# Sheet1.net
KiCad netlist of a schematic drawn in Altium Designer
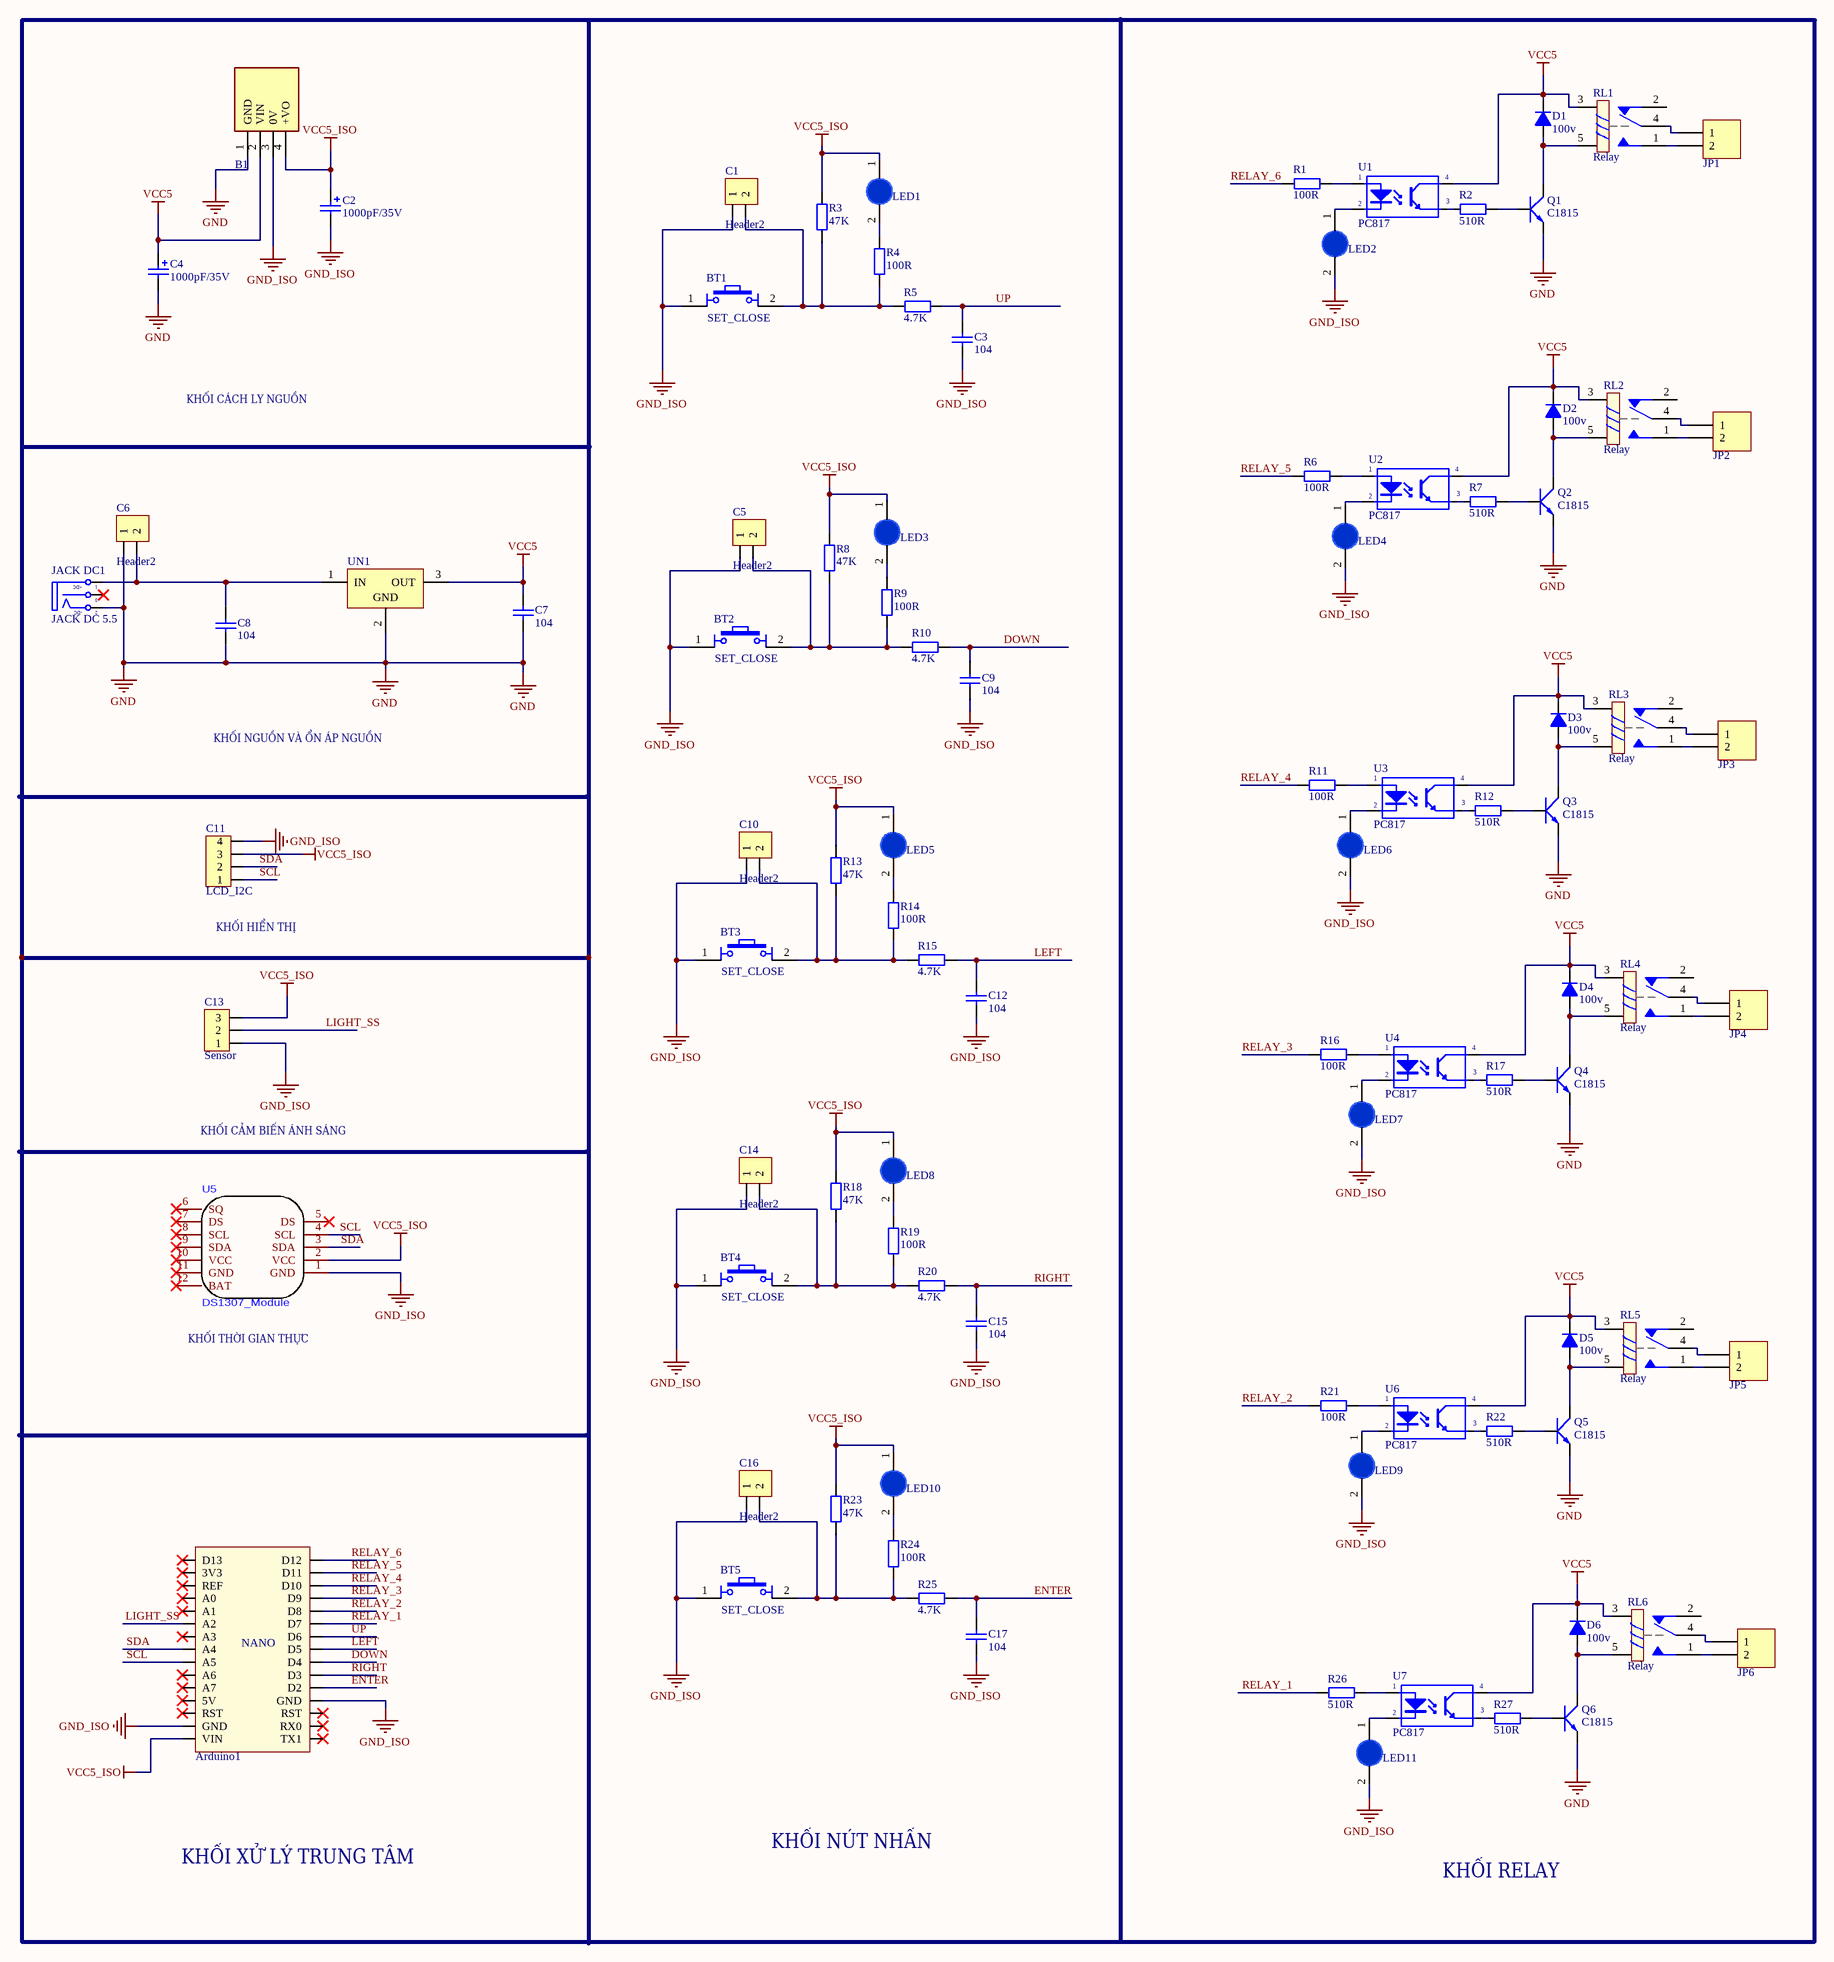
[diagram p0: Sheet1.SchDoc]

(export (version "E")
  (design (tool "Eeschema 10.0.6"))
  (components
    (comp (ref "Arduino1")
      (value "Arduino Nano")
      (footprint "Arduino Nano")
      (description "Arduino NANO")
      (libsource (lib "myLib_v1") (part "Arduino Nano"))
    )
    (comp (ref "B1")
      (value "B0505S1W")
      (footprint "B0505S1W")
      (description "Power Supply")
      (fields (field (name "MANUFACTURER_PART_NUMBER") "B0505S-1W"))
      (libsource (lib "myLib_v1") (part "B0505S1W"))
    )
    (comp (ref "BT1")
      (value "SET_CLOSE")
      (footprint "Nut Nhan 4 Chan Cam 6x6")
      (description "Nut Nhan 4 Chan 6x6mm")
      (libsource (lib "Altium_Lib_by_KhueNguyenCreator") (part "Nut Nhan 4 Chan Cam 6x6"))
    )
    (comp (ref "BT2")
      (value "SET_CLOSE")
      (footprint "Nut Nhan 4 Chan Cam 6x6")
      (description "Nut Nhan 4 Chan 6x6mm")
      (libsource (lib "Altium_Lib_by_KhueNguyenCreator") (part "Nut Nhan 4 Chan Cam 6x6"))
    )
    (comp (ref "BT3")
      (value "SET_CLOSE")
      (footprint "Nut Nhan 4 Chan Cam 6x6")
      (description "Nut Nhan 4 Chan 6x6mm")
      (libsource (lib "Altium_Lib_by_KhueNguyenCreator") (part "Nut Nhan 4 Chan Cam 6x6"))
    )
    (comp (ref "BT4")
      (value "SET_CLOSE")
      (footprint "Nut Nhan 4 Chan Cam 6x6")
      (description "Nut Nhan 4 Chan 6x6mm")
      (libsource (lib "Altium_Lib_by_KhueNguyenCreator") (part "Nut Nhan 4 Chan Cam 6x6"))
    )
    (comp (ref "BT5")
      (value "SET_CLOSE")
      (footprint "Nut Nhan 4 Chan Cam 6x6")
      (description "Nut Nhan 4 Chan 6x6mm")
      (libsource (lib "Altium_Lib_by_KhueNguyenCreator") (part "Nut Nhan 4 Chan Cam 6x6"))
    )
    (comp (ref "C1")
      (value "Header2")
      (footprint "Header2")
      (description "Header IDC, 2 x 1 Pin Vertical 2.54mm Pitch (Non-Boxed, Male)")
      (fields
        (field (name "MANUFACTURER") "Würth Elektronik eiSos GmbH")
        (field (name "PARTNO") "613002143121")
        (field (name "CREATED BY") "Karrer Zheng")
      )
      (libsource (lib "myLib_v1") (part "Header2"))
    )
    (comp (ref "C2")
      (value "1000pF/35V")
      (footprint "CP2/5")
      (description "Polarized Capacitor (Surface Mount)")
      (fields (field (name "Comment") "Cap Pol3") (field (name "PUBLISHER") "Altium Limited"))
      (libsource (lib "myLib_v1") (part "Cap Pol3"))
    )
    (comp (ref "C3")
      (value "104")
      (footprint "tu gom")
      (description "Cắm")
      (libsource (lib "Altium_Lib_by_KhueNguyenCreator") (part "Tu gom 104 50V"))
    )
    (comp (ref "C4")
      (value "1000pF/35V")
      (footprint "CP2/5")
      (description "Polarized Capacitor (Surface Mount)")
      (fields (field (name "Comment") "Cap Pol3") (field (name "PUBLISHER") "Altium Limited"))
      (libsource (lib "myLib_v1") (part "Cap Pol3"))
    )
    (comp (ref "C5")
      (value "Header2")
      (footprint "Header2")
      (description "Header IDC, 2 x 1 Pin Vertical 2.54mm Pitch (Non-Boxed, Male)")
      (fields
        (field (name "MANUFACTURER") "Würth Elektronik eiSos GmbH")
        (field (name "PARTNO") "613002143121")
        (field (name "CREATED BY") "Karrer Zheng")
      )
      (libsource (lib "myLib_v1") (part "Header2"))
    )
    (comp (ref "C6")
      (value "Header2")
      (footprint "Header2")
      (description "Header IDC, 2 x 1 Pin Vertical 2.54mm Pitch (Non-Boxed, Male)")
      (fields
        (field (name "MANUFACTURER") "Würth Elektronik eiSos GmbH")
        (field (name "PARTNO") "613002143121")
        (field (name "CREATED BY") "Karrer Zheng")
      )
      (libsource (lib "myLib_v1") (part "Header2"))
    )
    (comp (ref "C7")
      (value "104")
      (footprint "tu gom")
      (description "Cắm")
      (libsource (lib "Altium_Lib_by_KhueNguyenCreator") (part "Tu gom 104 50V"))
    )
    (comp (ref "C8")
      (value "104")
      (footprint "tu gom")
      (description "Cắm")
      (libsource (lib "Altium_Lib_by_KhueNguyenCreator") (part "Tu gom 104 50V"))
    )
    (comp (ref "C9")
      (value "104")
      (footprint "tu gom")
      (description "Cắm")
      (libsource (lib "Altium_Lib_by_KhueNguyenCreator") (part "Tu gom 104 50V"))
    )
    (comp (ref "C10")
      (value "Header2")
      (footprint "Header2")
      (description "Header IDC, 2 x 1 Pin Vertical 2.54mm Pitch (Non-Boxed, Male)")
      (fields
        (field (name "MANUFACTURER") "Würth Elektronik eiSos GmbH")
        (field (name "PARTNO") "613002143121")
        (field (name "CREATED BY") "Karrer Zheng")
      )
      (libsource (lib "myLib_v1") (part "Header2"))
    )
    (comp (ref "C11")
      (value "LCD_I2C")
      (footprint "Header4")
      (description "Header IDC, 4 x 1 Pin Vertical 2.54mm Pitch (Non-Boxed, Male)")
      (fields
        (field (name "MANUFACTURER") "Würth Elektronik eiSos GmbH")
        (field (name "PARTNO") "613002143121")
        (field (name "CREATED BY") "Karrer Zheng")
      )
      (libsource (lib "myLib_v1") (part "Header4"))
    )
    (comp (ref "C12")
      (value "104")
      (footprint "tu gom")
      (description "Cắm")
      (libsource (lib "Altium_Lib_by_KhueNguyenCreator") (part "Tu gom 104 50V"))
    )
    (comp (ref "C13")
      (value "Sensor")
      (footprint "Header3")
      (description "Header IDC, 3 x 1 Pin Vertical 2.54mm Pitch (Non-Boxed, Male)")
      (fields
        (field (name "MANUFACTURER") "Würth Elektronik eiSos GmbH")
        (field (name "PARTNO") "613002143121")
        (field (name "CREATED BY") "Karrer Zheng")
      )
      (libsource (lib "myLib_v1") (part "Header3"))
    )
    (comp (ref "C14")
      (value "Header2")
      (footprint "Header2")
      (description "Header IDC, 2 x 1 Pin Vertical 2.54mm Pitch (Non-Boxed, Male)")
      (fields
        (field (name "MANUFACTURER") "Würth Elektronik eiSos GmbH")
        (field (name "PARTNO") "613002143121")
        (field (name "CREATED BY") "Karrer Zheng")
      )
      (libsource (lib "myLib_v1") (part "Header2"))
    )
    (comp (ref "C15")
      (value "104")
      (footprint "tu gom")
      (description "Cắm")
      (libsource (lib "Altium_Lib_by_KhueNguyenCreator") (part "Tu gom 104 50V"))
    )
    (comp (ref "C16")
      (value "Header2")
      (footprint "Header2")
      (description "Header IDC, 2 x 1 Pin Vertical 2.54mm Pitch (Non-Boxed, Male)")
      (fields
        (field (name "MANUFACTURER") "Würth Elektronik eiSos GmbH")
        (field (name "PARTNO") "613002143121")
        (field (name "CREATED BY") "Karrer Zheng")
      )
      (libsource (lib "myLib_v1") (part "Header2"))
    )
    (comp (ref "C17")
      (value "104")
      (footprint "tu gom")
      (description "Cắm")
      (libsource (lib "Altium_Lib_by_KhueNguyenCreator") (part "Tu gom 104 50V"))
    )
    (comp (ref "D1")
      (value "100v")
      (footprint "DIODE 0.5A")
      (description "Cắm")
      (libsource (lib "Altium_Lib_by_KhueNguyenCreator") (part "Diode 1N4148"))
    )
    (comp (ref "D2")
      (value "100v")
      (footprint "DIODE 0.5A")
      (description "Cắm")
      (libsource (lib "Altium_Lib_by_KhueNguyenCreator") (part "Diode 1N4148"))
    )
    (comp (ref "D3")
      (value "100v")
      (footprint "DIODE 0.5A")
      (description "Cắm")
      (libsource (lib "Altium_Lib_by_KhueNguyenCreator") (part "Diode 1N4148"))
    )
    (comp (ref "D4")
      (value "100v")
      (footprint "DIODE 0.5A")
      (description "Cắm")
      (libsource (lib "Altium_Lib_by_KhueNguyenCreator") (part "Diode 1N4148"))
    )
    (comp (ref "D5")
      (value "100v")
      (footprint "DIODE 0.5A")
      (description "Cắm")
      (libsource (lib "Altium_Lib_by_KhueNguyenCreator") (part "Diode 1N4148"))
    )
    (comp (ref "D6")
      (value "100v")
      (footprint "DIODE 0.5A")
      (description "Cắm")
      (libsource (lib "Altium_Lib_by_KhueNguyenCreator") (part "Diode 1N4148"))
    )
    (comp (ref "JACK DC1")
      (value "JACK DC 5.5")
      (footprint "JACK DC 5.5")
      (libsource (lib "Altium_Lib_by_KhueNguyenCreator") (part "JACK DC 5.5"))
    )
    (comp (ref "JP1")
      (value "Header 2_1")
      (footprint "HED2")
      (description "Header, 2-Pin")
      (fields (field (name "MANUFACTURER") "Generic Components"))
      (libsource (lib "myLib_v1") (part "Header 2_1"))
    )
    (comp (ref "JP2")
      (value "Header 2_1")
      (footprint "HED2")
      (description "Header, 2-Pin")
      (fields (field (name "MANUFACTURER") "Generic Components"))
      (libsource (lib "myLib_v1") (part "Header 2_1"))
    )
    (comp (ref "JP3")
      (value "Header 2_1")
      (footprint "HED2")
      (description "Header, 2-Pin")
      (fields (field (name "MANUFACTURER") "Generic Components"))
      (libsource (lib "myLib_v1") (part "Header 2_1"))
    )
    (comp (ref "JP4")
      (value "Header 2_1")
      (footprint "HED2")
      (description "Header, 2-Pin")
      (fields (field (name "MANUFACTURER") "Generic Components"))
      (libsource (lib "myLib_v1") (part "Header 2_1"))
    )
    (comp (ref "JP5")
      (value "Header 2_1")
      (footprint "HED2")
      (description "Header, 2-Pin")
      (fields (field (name "MANUFACTURER") "Generic Components"))
      (libsource (lib "myLib_v1") (part "Header 2_1"))
    )
    (comp (ref "JP6")
      (value "Header 2_1")
      (footprint "HED2")
      (description "Header, 2-Pin")
      (fields (field (name "MANUFACTURER") "Generic Components"))
      (libsource (lib "myLib_v1") (part "Header 2_1"))
    )
    (comp (ref "LED1")
      (value "LED 3mm")
      (footprint "LED-3MM-BLUE")
      (description "Cắm")
      (libsource (lib "myLib_v1") (part "LED 3mm Xanh Duong"))
    )
    (comp (ref "LED2")
      (value "LED 3mm")
      (footprint "LED-3MM-BLUE")
      (description "Cắm")
      (libsource (lib "myLib_v1") (part "LED 3mm Xanh Duong"))
    )
    (comp (ref "LED3")
      (value "LED 3mm")
      (footprint "LED-3MM-BLUE")
      (description "Cắm")
      (libsource (lib "myLib_v1") (part "LED 3mm Xanh Duong"))
    )
    (comp (ref "LED4")
      (value "LED 3mm")
      (footprint "LED-3MM-BLUE")
      (description "Cắm")
      (libsource (lib "myLib_v1") (part "LED 3mm Xanh Duong"))
    )
    (comp (ref "LED5")
      (value "LED 3mm")
      (footprint "LED-3MM-BLUE")
      (description "Cắm")
      (libsource (lib "myLib_v1") (part "LED 3mm Xanh Duong"))
    )
    (comp (ref "LED6")
      (value "LED 3mm")
      (footprint "LED-3MM-BLUE")
      (description "Cắm")
      (libsource (lib "myLib_v1") (part "LED 3mm Xanh Duong"))
    )
    (comp (ref "LED7")
      (value "LED 3mm")
      (footprint "LED-3MM-BLUE")
      (description "Cắm")
      (libsource (lib "myLib_v1") (part "LED 3mm Xanh Duong"))
    )
    (comp (ref "LED8")
      (value "LED 3mm")
      (footprint "LED-3MM-BLUE")
      (description "Cắm")
      (libsource (lib "myLib_v1") (part "LED 3mm Xanh Duong"))
    )
    (comp (ref "LED9")
      (value "LED 3mm")
      (footprint "LED-3MM-BLUE")
      (description "Cắm")
      (libsource (lib "myLib_v1") (part "LED 3mm Xanh Duong"))
    )
    (comp (ref "LED10")
      (value "LED 3mm")
      (footprint "LED-3MM-BLUE")
      (description "Cắm")
      (libsource (lib "myLib_v1") (part "LED 3mm Xanh Duong"))
    )
    (comp (ref "LED11")
      (value "LED 3mm")
      (footprint "LED-3MM-BLUE")
      (description "Cắm")
      (libsource (lib "myLib_v1") (part "LED 3mm Xanh Duong"))
    )
    (comp (ref "Q1")
      (value "C1815")
      (footprint "C1815_cam")
      (description "NPN 600mW, ECB")
      (libsource (lib "myLib_v1") (part "C1815"))
    )
    (comp (ref "Q2")
      (value "C1815")
      (footprint "C1815_cam")
      (description "NPN 600mW, ECB")
      (libsource (lib "myLib_v1") (part "C1815"))
    )
    (comp (ref "Q3")
      (value "C1815")
      (footprint "C1815_cam")
      (description "NPN 600mW, ECB")
      (libsource (lib "myLib_v1") (part "C1815"))
    )
    (comp (ref "Q4")
      (value "C1815")
      (footprint "C1815_cam")
      (description "NPN 600mW, ECB")
      (libsource (lib "myLib_v1") (part "C1815"))
    )
    (comp (ref "Q5")
      (value "C1815")
      (footprint "C1815_cam")
      (description "NPN 600mW, ECB")
      (libsource (lib "myLib_v1") (part "C1815"))
    )
    (comp (ref "Q6")
      (value "C1815")
      (footprint "C1815_cam")
      (description "NPN 600mW, ECB")
      (libsource (lib "myLib_v1") (part "C1815"))
    )
    (comp (ref "R1")
      (value "100R")
      (footprint "R1/4W")
      (description "Resistor 1/4W")
      (libsource (lib "myLib_v1") (part "R1/4W"))
    )
    (comp (ref "R2")
      (value "510R")
      (footprint "R1/4W")
      (description "Resistor 1/4W")
      (libsource (lib "myLib_v1") (part "R1/4W"))
    )
    (comp (ref "R3")
      (value "47K")
      (footprint "R1/4W")
      (description "Resistor 1/4W")
      (libsource (lib "myLib_v1") (part "R1/4W"))
    )
    (comp (ref "R4")
      (value "100R")
      (footprint "R1/4W")
      (description "Resistor 1/4W")
      (libsource (lib "myLib_v1") (part "R1/4W"))
    )
    (comp (ref "R5")
      (value "4.7K")
      (footprint "R1/4W")
      (description "Resistor 1/4W")
      (libsource (lib "myLib_v1") (part "R1/4W"))
    )
    (comp (ref "R6")
      (value "100R")
      (footprint "R1/4W")
      (description "Resistor 1/4W")
      (libsource (lib "myLib_v1") (part "R1/4W"))
    )
    (comp (ref "R7")
      (value "510R")
      (footprint "R1/4W")
      (description "Resistor 1/4W")
      (libsource (lib "myLib_v1") (part "R1/4W"))
    )
    (comp (ref "R8")
      (value "47K")
      (footprint "R1/4W")
      (description "Resistor 1/4W")
      (libsource (lib "myLib_v1") (part "R1/4W"))
    )
    (comp (ref "R9")
      (value "100R")
      (footprint "R1/4W")
      (description "Resistor 1/4W")
      (libsource (lib "myLib_v1") (part "R1/4W"))
    )
    (comp (ref "R10")
      (value "4.7K")
      (footprint "R1/4W")
      (description "Resistor 1/4W")
      (libsource (lib "myLib_v1") (part "R1/4W"))
    )
    (comp (ref "R11")
      (value "100R")
      (footprint "R1/4W")
      (description "Resistor 1/4W")
      (libsource (lib "myLib_v1") (part "R1/4W"))
    )
    (comp (ref "R12")
      (value "510R")
      (footprint "R1/4W")
      (description "Resistor 1/4W")
      (libsource (lib "myLib_v1") (part "R1/4W"))
    )
    (comp (ref "R13")
      (value "47K")
      (footprint "R1/4W")
      (description "Resistor 1/4W")
      (libsource (lib "myLib_v1") (part "R1/4W"))
    )
    (comp (ref "R14")
      (value "100R")
      (footprint "R1/4W")
      (description "Resistor 1/4W")
      (libsource (lib "myLib_v1") (part "R1/4W"))
    )
    (comp (ref "R15")
      (value "4.7K")
      (footprint "R1/4W")
      (description "Resistor 1/4W")
      (libsource (lib "myLib_v1") (part "R1/4W"))
    )
    (comp (ref "R16")
      (value "100R")
      (footprint "R1/4W")
      (description "Resistor 1/4W")
      (libsource (lib "myLib_v1") (part "R1/4W"))
    )
    (comp (ref "R17")
      (value "510R")
      (footprint "R1/4W")
      (description "Resistor 1/4W")
      (libsource (lib "myLib_v1") (part "R1/4W"))
    )
    (comp (ref "R18")
      (value "47K")
      (footprint "R1/4W")
      (description "Resistor 1/4W")
      (libsource (lib "myLib_v1") (part "R1/4W"))
    )
    (comp (ref "R19")
      (value "100R")
      (footprint "R1/4W")
      (description "Resistor 1/4W")
      (libsource (lib "myLib_v1") (part "R1/4W"))
    )
    (comp (ref "R20")
      (value "4.7K")
      (footprint "R1/4W")
      (description "Resistor 1/4W")
      (libsource (lib "myLib_v1") (part "R1/4W"))
    )
    (comp (ref "R21")
      (value "100R")
      (footprint "R1/4W")
      (description "Resistor 1/4W")
      (libsource (lib "myLib_v1") (part "R1/4W"))
    )
    (comp (ref "R22")
      (value "510R")
      (footprint "R1/4W")
      (description "Resistor 1/4W")
      (libsource (lib "myLib_v1") (part "R1/4W"))
    )
    (comp (ref "R23")
      (value "47K")
      (footprint "R1/4W")
      (description "Resistor 1/4W")
      (libsource (lib "myLib_v1") (part "R1/4W"))
    )
    (comp (ref "R24")
      (value "100R")
      (footprint "R1/4W")
      (description "Resistor 1/4W")
      (libsource (lib "myLib_v1") (part "R1/4W"))
    )
    (comp (ref "R25")
      (value "4.7K")
      (footprint "R1/4W")
      (description "Resistor 1/4W")
      (libsource (lib "myLib_v1") (part "R1/4W"))
    )
    (comp (ref "R26")
      (value "510R")
      (footprint "R1/4W")
      (description "Resistor 1/4W")
      (libsource (lib "myLib_v1") (part "R1/4W"))
    )
    (comp (ref "R27")
      (value "510R")
      (footprint "R1/4W")
      (description "Resistor 1/4W")
      (libsource (lib "myLib_v1") (part "R1/4W"))
    )
    (comp (ref "RL1")
      (value "Relay")
      (footprint "RELAY_SRA_05VDC_CL")
      (description "Relay 5 Chan")
      (libsource (lib "myLib_v1") (part "RL_SRA-05VDC-CL"))
    )
    (comp (ref "RL2")
      (value "Relay")
      (footprint "RELAY_SRA_05VDC_CL")
      (description "Relay 5 Chan")
      (libsource (lib "myLib_v1") (part "RL_SRA-05VDC-CL"))
    )
    (comp (ref "RL3")
      (value "Relay")
      (footprint "RELAY_SRA_05VDC_CL")
      (description "Relay 5 Chan")
      (libsource (lib "myLib_v1") (part "RL_SRA-05VDC-CL"))
    )
    (comp (ref "RL4")
      (value "Relay")
      (footprint "RELAY_SRA_05VDC_CL")
      (description "Relay 5 Chan")
      (libsource (lib "myLib_v1") (part "RL_SRA-05VDC-CL"))
    )
    (comp (ref "RL5")
      (value "Relay")
      (footprint "RELAY_SRA_05VDC_CL")
      (description "Relay 5 Chan")
      (libsource (lib "myLib_v1") (part "RL_SRA-05VDC-CL"))
    )
    (comp (ref "RL6")
      (value "Relay")
      (footprint "RELAY_SRA_05VDC_CL")
      (description "Relay 5 Chan")
      (libsource (lib "myLib_v1") (part "RL_SRA-05VDC-CL"))
    )
    (comp (ref "U1")
      (value "PC817")
      (footprint "DIP4/W0.3")
      (description "Single Opto")
      (libsource (lib "myLib_v1") (part "PC817"))
    )
    (comp (ref "U2")
      (value "PC817")
      (footprint "DIP4/W0.3")
      (description "Single Opto")
      (libsource (lib "myLib_v1") (part "PC817"))
    )
    (comp (ref "U3")
      (value "PC817")
      (footprint "DIP4/W0.3")
      (description "Single Opto")
      (libsource (lib "myLib_v1") (part "PC817"))
    )
    (comp (ref "U4")
      (value "PC817")
      (footprint "DIP4/W0.3")
      (description "Single Opto")
      (libsource (lib "myLib_v1") (part "PC817"))
    )
    (comp (ref "U5")
      (value "DS1307_Module")
      (footprint "DS1307 MODULE")
      (libsource (lib "myLib_v1") (part "DS1307_Module"))
    )
    (comp (ref "U6")
      (value "PC817")
      (footprint "DIP4/W0.3")
      (description "Single Opto")
      (libsource (lib "myLib_v1") (part "PC817"))
    )
    (comp (ref "U7")
      (value "PC817")
      (footprint "DIP4/W0.3")
      (description "Single Opto")
      (libsource (lib "myLib_v1") (part "PC817"))
    )
    (comp (ref "UN1")
      (value "L78M05CP")
      (footprint "QTO-220H2")
      (description "Positive Voltage Regulator")
      (fields (field (name "PUBLISHER") "Altium Limited"))
      (libsource (lib "syhaunguyen") (part "L78M05CP"))
    )
  )
  (nets
    (net (code "1") (name "/DOWN") (class "Default")
      (node (ref "Arduino1") (pin "D4") (pinfunction "D4_D4") (pintype "passive"))
      (node (ref "C9") (pin "1") (pinfunction "1_1") (pintype "passive"))
      (node (ref "R10") (pin "1") (pinfunction "1_1") (pintype "passive"))
    )
    (net (code "2") (name "/ENTER") (class "Default")
      (node (ref "Arduino1") (pin "D2") (pinfunction "D2_D2") (pintype "passive"))
      (node (ref "C17") (pin "1") (pinfunction "1_1") (pintype "passive"))
      (node (ref "R25") (pin "1") (pinfunction "1_1") (pintype "passive"))
    )
    (net (code "3") (name "/LEFT") (class "Default")
      (node (ref "Arduino1") (pin "D5") (pinfunction "D5_D5") (pintype "passive"))
      (node (ref "C12") (pin "1") (pinfunction "1_1") (pintype "passive"))
      (node (ref "R15") (pin "1") (pinfunction "1_1") (pintype "passive"))
    )
    (net (code "4") (name "/LIGHT_SS") (class "Default")
      (node (ref "Arduino1") (pin "A2") (pinfunction "A2_A2") (pintype "passive"))
      (node (ref "C13") (pin "2") (pinfunction "2_2") (pintype "passive"))
    )
    (net (code "5") (name "/RELAY_1") (class "Default")
      (node (ref "Arduino1") (pin "D7") (pinfunction "D7_D7") (pintype "passive"))
      (node (ref "R26") (pin "1") (pinfunction "1_1") (pintype "passive"))
    )
    (net (code "6") (name "/RELAY_2") (class "Default")
      (node (ref "Arduino1") (pin "D8") (pinfunction "D8_D8") (pintype "passive"))
      (node (ref "R21") (pin "1") (pinfunction "1_1") (pintype "passive"))
    )
    (net (code "7") (name "/RELAY_3") (class "Default")
      (node (ref "Arduino1") (pin "D9") (pinfunction "D9_D9") (pintype "passive"))
      (node (ref "R16") (pin "1") (pinfunction "1_1") (pintype "passive"))
    )
    (net (code "8") (name "/RELAY_4") (class "Default")
      (node (ref "Arduino1") (pin "D10") (pinfunction "D10_D10") (pintype "passive"))
      (node (ref "R11") (pin "1") (pinfunction "1_1") (pintype "passive"))
    )
    (net (code "9") (name "/RELAY_5") (class "Default")
      (node (ref "Arduino1") (pin "D11") (pinfunction "D11_D11") (pintype "passive"))
      (node (ref "R6") (pin "1") (pinfunction "1_1") (pintype "passive"))
    )
    (net (code "10") (name "/RELAY_6") (class "Default")
      (node (ref "Arduino1") (pin "D12") (pinfunction "D12_D12") (pintype "passive"))
      (node (ref "R1") (pin "1") (pinfunction "1_1") (pintype "passive"))
    )
    (net (code "11") (name "/RIGHT") (class "Default")
      (node (ref "Arduino1") (pin "D3") (pinfunction "D3_D3") (pintype "passive"))
      (node (ref "C15") (pin "1") (pinfunction "1_1") (pintype "passive"))
      (node (ref "R20") (pin "1") (pinfunction "1_1") (pintype "passive"))
    )
    (net (code "12") (name "/SCL") (class "Default")
      (node (ref "Arduino1") (pin "A5") (pinfunction "A5_A5") (pintype "passive"))
      (node (ref "C11") (pin "1") (pinfunction "1_1") (pintype "passive"))
      (node (ref "U5") (pin "4") (pinfunction "SCL_4") (pintype "passive"))
    )
    (net (code "13") (name "/SDA") (class "Default")
      (node (ref "Arduino1") (pin "A4") (pinfunction "A4_A4") (pintype "passive"))
      (node (ref "C11") (pin "2") (pinfunction "2_2") (pintype "passive"))
      (node (ref "U5") (pin "3") (pinfunction "SDA_3") (pintype "passive"))
    )
    (net (code "14") (name "/UP") (class "Default")
      (node (ref "Arduino1") (pin "D6") (pinfunction "D6_D6") (pintype "passive"))
      (node (ref "C3") (pin "1") (pinfunction "1_1") (pintype "passive"))
      (node (ref "R5") (pin "1") (pinfunction "1_1") (pintype "passive"))
    )
    (net (code "15") (name "GND") (class "Default")
      (node (ref "B1") (pin "1") (pinfunction "GND_1") (pintype "passive"))
      (node (ref "C4") (pin "2") (pinfunction "2_2") (pintype "passive"))
      (node (ref "C6") (pin "1") (pinfunction "1_1") (pintype "passive"))
      (node (ref "C7") (pin "2") (pinfunction "2_2") (pintype "passive"))
      (node (ref "C8") (pin "2") (pinfunction "2_2") (pintype "passive"))
      (node (ref "JACK DC1") (pin "2") (pinfunction "TN_2") (pintype "passive"))
      (node (ref "Q1") (pin "1") (pinfunction "E_1") (pintype "passive"))
      (node (ref "Q2") (pin "1") (pinfunction "E_1") (pintype "passive"))
      (node (ref "Q3") (pin "1") (pinfunction "E_1") (pintype "passive"))
      (node (ref "Q4") (pin "1") (pinfunction "E_1") (pintype "passive"))
      (node (ref "Q5") (pin "1") (pinfunction "E_1") (pintype "passive"))
      (node (ref "Q6") (pin "1") (pinfunction "E_1") (pintype "passive"))
      (node (ref "UN1") (pin "2") (pinfunction "GND_2") (pintype "power_in"))
    )
    (net (code "16") (name "GND_ISO") (class "Default")
      (node (ref "Arduino1") (pin "GND") (pinfunction "GND_GND") (pintype "passive"))
      (node (ref "B1") (pin "3") (pinfunction "0V_3") (pintype "passive"))
      (node (ref "BT1") (pin "1") (pintype "passive"))
      (node (ref "BT2") (pin "1") (pintype "passive"))
      (node (ref "BT3") (pin "1") (pintype "passive"))
      (node (ref "BT4") (pin "1") (pintype "passive"))
      (node (ref "BT5") (pin "1") (pintype "passive"))
      (node (ref "C1") (pin "1") (pinfunction "1_1") (pintype "passive"))
      (node (ref "C10") (pin "1") (pinfunction "1_1") (pintype "passive"))
      (node (ref "C11") (pin "4") (pinfunction "4_4") (pintype "passive"))
      (node (ref "C12") (pin "2") (pinfunction "2_2") (pintype "passive"))
      (node (ref "C13") (pin "1") (pinfunction "1_1") (pintype "passive"))
      (node (ref "C14") (pin "1") (pinfunction "1_1") (pintype "passive"))
      (node (ref "C15") (pin "2") (pinfunction "2_2") (pintype "passive"))
      (node (ref "C16") (pin "1") (pinfunction "1_1") (pintype "passive"))
      (node (ref "C17") (pin "2") (pinfunction "2_2") (pintype "passive"))
      (node (ref "C2") (pin "2") (pinfunction "2_2") (pintype "passive"))
      (node (ref "C3") (pin "2") (pinfunction "2_2") (pintype "passive"))
      (node (ref "C5") (pin "1") (pinfunction "1_1") (pintype "passive"))
      (node (ref "C9") (pin "2") (pinfunction "2_2") (pintype "passive"))
      (node (ref "LED11") (pin "2") (pinfunction "K_2") (pintype "passive"))
      (node (ref "LED2") (pin "2") (pinfunction "K_2") (pintype "passive"))
      (node (ref "LED4") (pin "2") (pinfunction "K_2") (pintype "passive"))
      (node (ref "LED6") (pin "2") (pinfunction "K_2") (pintype "passive"))
      (node (ref "LED7") (pin "2") (pinfunction "K_2") (pintype "passive"))
      (node (ref "LED9") (pin "2") (pinfunction "K_2") (pintype "passive"))
      (node (ref "U5") (pin "1") (pinfunction "GND_1") (pintype "passive"))
    )
    (net (code "17") (name "Net-(BT1-Pad2)") (class "Default")
      (node (ref "BT1") (pin "2") (pintype "passive"))
      (node (ref "C1") (pin "2") (pinfunction "2_2") (pintype "passive"))
      (node (ref "R3") (pin "1") (pinfunction "1_1") (pintype "passive"))
      (node (ref "R4") (pin "1") (pinfunction "1_1") (pintype "passive"))
      (node (ref "R5") (pin "2") (pinfunction "2_2") (pintype "passive"))
    )
    (net (code "18") (name "Net-(BT2-Pad2)") (class "Default")
      (node (ref "BT2") (pin "2") (pintype "passive"))
      (node (ref "C5") (pin "2") (pinfunction "2_2") (pintype "passive"))
      (node (ref "R10") (pin "2") (pinfunction "2_2") (pintype "passive"))
      (node (ref "R8") (pin "1") (pinfunction "1_1") (pintype "passive"))
      (node (ref "R9") (pin "1") (pinfunction "1_1") (pintype "passive"))
    )
    (net (code "19") (name "Net-(BT3-Pad2)") (class "Default")
      (node (ref "BT3") (pin "2") (pintype "passive"))
      (node (ref "C10") (pin "2") (pinfunction "2_2") (pintype "passive"))
      (node (ref "R13") (pin "1") (pinfunction "1_1") (pintype "passive"))
      (node (ref "R14") (pin "1") (pinfunction "1_1") (pintype "passive"))
      (node (ref "R15") (pin "2") (pinfunction "2_2") (pintype "passive"))
    )
    (net (code "20") (name "Net-(BT4-Pad2)") (class "Default")
      (node (ref "BT4") (pin "2") (pintype "passive"))
      (node (ref "C14") (pin "2") (pinfunction "2_2") (pintype "passive"))
      (node (ref "R18") (pin "1") (pinfunction "1_1") (pintype "passive"))
      (node (ref "R19") (pin "1") (pinfunction "1_1") (pintype "passive"))
      (node (ref "R20") (pin "2") (pinfunction "2_2") (pintype "passive"))
    )
    (net (code "21") (name "Net-(BT5-Pad2)") (class "Default")
      (node (ref "BT5") (pin "2") (pintype "passive"))
      (node (ref "C16") (pin "2") (pinfunction "2_2") (pintype "passive"))
      (node (ref "R23") (pin "1") (pinfunction "1_1") (pintype "passive"))
      (node (ref "R24") (pin "1") (pinfunction "1_1") (pintype "passive"))
      (node (ref "R25") (pin "2") (pinfunction "2_2") (pintype "passive"))
    )
    (net (code "22") (name "Net-(D1-A)") (class "Default")
      (node (ref "D1") (pin "1") (pinfunction "A_1") (pintype "passive"))
      (node (ref "Q1") (pin "2") (pinfunction "C_2") (pintype "passive"))
      (node (ref "RL1") (pin "5") (pinfunction "5_5") (pintype "passive"))
    )
    (net (code "23") (name "Net-(D2-A)") (class "Default")
      (node (ref "D2") (pin "1") (pinfunction "A_1") (pintype "passive"))
      (node (ref "Q2") (pin "2") (pinfunction "C_2") (pintype "passive"))
      (node (ref "RL2") (pin "5") (pinfunction "5_5") (pintype "passive"))
    )
    (net (code "24") (name "Net-(D3-A)") (class "Default")
      (node (ref "D3") (pin "1") (pinfunction "A_1") (pintype "passive"))
      (node (ref "Q3") (pin "2") (pinfunction "C_2") (pintype "passive"))
      (node (ref "RL3") (pin "5") (pinfunction "5_5") (pintype "passive"))
    )
    (net (code "25") (name "Net-(D4-A)") (class "Default")
      (node (ref "D4") (pin "1") (pinfunction "A_1") (pintype "passive"))
      (node (ref "Q4") (pin "2") (pinfunction "C_2") (pintype "passive"))
      (node (ref "RL4") (pin "5") (pinfunction "5_5") (pintype "passive"))
    )
    (net (code "26") (name "Net-(D5-A)") (class "Default")
      (node (ref "D5") (pin "1") (pinfunction "A_1") (pintype "passive"))
      (node (ref "Q5") (pin "2") (pinfunction "C_2") (pintype "passive"))
      (node (ref "RL5") (pin "5") (pinfunction "5_5") (pintype "passive"))
    )
    (net (code "27") (name "Net-(D6-A)") (class "Default")
      (node (ref "D6") (pin "1") (pinfunction "A_1") (pintype "passive"))
      (node (ref "Q6") (pin "2") (pinfunction "C_2") (pintype "passive"))
      (node (ref "RL6") (pin "5") (pinfunction "5_5") (pintype "passive"))
    )
    (net (code "28") (name "Net-(JACK DC1-T)") (class "Default")
      (node (ref "C6") (pin "2") (pinfunction "2_2") (pintype "passive"))
      (node (ref "C8") (pin "1") (pinfunction "1_1") (pintype "passive"))
      (node (ref "JACK DC1") (pin "1") (pinfunction "T_1") (pintype "passive"))
      (node (ref "UN1") (pin "1") (pinfunction "IN_1") (pintype "power_in"))
    )
    (net (code "29") (name "Net-(JP1-Pad1)") (class "Default")
      (node (ref "JP1") (pin "1") (pinfunction "1_1") (pintype "passive"))
      (node (ref "RL1") (pin "4") (pinfunction "4_4") (pintype "passive"))
    )
    (net (code "30") (name "Net-(JP1-Pad2)") (class "Default")
      (node (ref "JP1") (pin "2") (pinfunction "2_2") (pintype "passive"))
      (node (ref "RL1") (pin "1") (pinfunction "1_1") (pintype "passive"))
    )
    (net (code "31") (name "Net-(JP2-Pad1)") (class "Default")
      (node (ref "JP2") (pin "1") (pinfunction "1_1") (pintype "passive"))
      (node (ref "RL2") (pin "4") (pinfunction "4_4") (pintype "passive"))
    )
    (net (code "32") (name "Net-(JP2-Pad2)") (class "Default")
      (node (ref "JP2") (pin "2") (pinfunction "2_2") (pintype "passive"))
      (node (ref "RL2") (pin "1") (pinfunction "1_1") (pintype "passive"))
    )
    (net (code "33") (name "Net-(JP3-Pad1)") (class "Default")
      (node (ref "JP3") (pin "1") (pinfunction "1_1") (pintype "passive"))
      (node (ref "RL3") (pin "4") (pinfunction "4_4") (pintype "passive"))
    )
    (net (code "34") (name "Net-(JP3-Pad2)") (class "Default")
      (node (ref "JP3") (pin "2") (pinfunction "2_2") (pintype "passive"))
      (node (ref "RL3") (pin "1") (pinfunction "1_1") (pintype "passive"))
    )
    (net (code "35") (name "Net-(JP4-Pad1)") (class "Default")
      (node (ref "JP4") (pin "1") (pinfunction "1_1") (pintype "passive"))
      (node (ref "RL4") (pin "4") (pinfunction "4_4") (pintype "passive"))
    )
    (net (code "36") (name "Net-(JP4-Pad2)") (class "Default")
      (node (ref "JP4") (pin "2") (pinfunction "2_2") (pintype "passive"))
      (node (ref "RL4") (pin "1") (pinfunction "1_1") (pintype "passive"))
    )
    (net (code "37") (name "Net-(JP5-Pad1)") (class "Default")
      (node (ref "JP5") (pin "1") (pinfunction "1_1") (pintype "passive"))
      (node (ref "RL5") (pin "4") (pinfunction "4_4") (pintype "passive"))
    )
    (net (code "38") (name "Net-(JP5-Pad2)") (class "Default")
      (node (ref "JP5") (pin "2") (pinfunction "2_2") (pintype "passive"))
      (node (ref "RL5") (pin "1") (pinfunction "1_1") (pintype "passive"))
    )
    (net (code "39") (name "Net-(JP6-Pad1)") (class "Default")
      (node (ref "JP6") (pin "1") (pinfunction "1_1") (pintype "passive"))
      (node (ref "RL6") (pin "4") (pinfunction "4_4") (pintype "passive"))
    )
    (net (code "40") (name "Net-(JP6-Pad2)") (class "Default")
      (node (ref "JP6") (pin "2") (pinfunction "2_2") (pintype "passive"))
      (node (ref "RL6") (pin "1") (pinfunction "1_1") (pintype "passive"))
    )
    (net (code "41") (name "Net-(LED1-K)") (class "Default")
      (node (ref "LED1") (pin "2") (pinfunction "K_2") (pintype "passive"))
      (node (ref "R4") (pin "2") (pinfunction "2_2") (pintype "passive"))
    )
    (net (code "42") (name "Net-(LED2-A)") (class "Default")
      (node (ref "LED2") (pin "1") (pinfunction "A_1") (pintype "passive"))
      (node (ref "U1") (pin "2") (pinfunction "K_2") (pintype "passive"))
    )
    (net (code "43") (name "Net-(LED3-K)") (class "Default")
      (node (ref "LED3") (pin "2") (pinfunction "K_2") (pintype "passive"))
      (node (ref "R9") (pin "2") (pinfunction "2_2") (pintype "passive"))
    )
    (net (code "44") (name "Net-(LED4-A)") (class "Default")
      (node (ref "LED4") (pin "1") (pinfunction "A_1") (pintype "passive"))
      (node (ref "U2") (pin "2") (pinfunction "K_2") (pintype "passive"))
    )
    (net (code "45") (name "Net-(LED5-K)") (class "Default")
      (node (ref "LED5") (pin "2") (pinfunction "K_2") (pintype "passive"))
      (node (ref "R14") (pin "2") (pinfunction "2_2") (pintype "passive"))
    )
    (net (code "46") (name "Net-(LED6-A)") (class "Default")
      (node (ref "LED6") (pin "1") (pinfunction "A_1") (pintype "passive"))
      (node (ref "U3") (pin "2") (pinfunction "K_2") (pintype "passive"))
    )
    (net (code "47") (name "Net-(LED7-A)") (class "Default")
      (node (ref "LED7") (pin "1") (pinfunction "A_1") (pintype "passive"))
      (node (ref "U4") (pin "2") (pinfunction "K_2") (pintype "passive"))
    )
    (net (code "48") (name "Net-(LED8-K)") (class "Default")
      (node (ref "LED8") (pin "2") (pinfunction "K_2") (pintype "passive"))
      (node (ref "R19") (pin "2") (pinfunction "2_2") (pintype "passive"))
    )
    (net (code "49") (name "Net-(LED9-A)") (class "Default")
      (node (ref "LED9") (pin "1") (pinfunction "A_1") (pintype "passive"))
      (node (ref "U6") (pin "2") (pinfunction "K_2") (pintype "passive"))
    )
    (net (code "50") (name "Net-(LED10-K)") (class "Default")
      (node (ref "LED10") (pin "2") (pinfunction "K_2") (pintype "passive"))
      (node (ref "R24") (pin "2") (pinfunction "2_2") (pintype "passive"))
    )
    (net (code "51") (name "Net-(LED11-A)") (class "Default")
      (node (ref "LED11") (pin "1") (pinfunction "A_1") (pintype "passive"))
      (node (ref "U7") (pin "2") (pinfunction "K_2") (pintype "passive"))
    )
    (net (code "52") (name "Net-(Q1-B)") (class "Default")
      (node (ref "Q1") (pin "3") (pinfunction "B_3") (pintype "passive"))
      (node (ref "R2") (pin "2") (pinfunction "2_2") (pintype "passive"))
    )
    (net (code "53") (name "Net-(Q2-B)") (class "Default")
      (node (ref "Q2") (pin "3") (pinfunction "B_3") (pintype "passive"))
      (node (ref "R7") (pin "2") (pinfunction "2_2") (pintype "passive"))
    )
    (net (code "54") (name "Net-(Q3-B)") (class "Default")
      (node (ref "Q3") (pin "3") (pinfunction "B_3") (pintype "passive"))
      (node (ref "R12") (pin "2") (pinfunction "2_2") (pintype "passive"))
    )
    (net (code "55") (name "Net-(Q4-B)") (class "Default")
      (node (ref "Q4") (pin "3") (pinfunction "B_3") (pintype "passive"))
      (node (ref "R17") (pin "2") (pinfunction "2_2") (pintype "passive"))
    )
    (net (code "56") (name "Net-(Q5-B)") (class "Default")
      (node (ref "Q5") (pin "3") (pinfunction "B_3") (pintype "passive"))
      (node (ref "R22") (pin "2") (pinfunction "2_2") (pintype "passive"))
    )
    (net (code "57") (name "Net-(Q6-B)") (class "Default")
      (node (ref "Q6") (pin "3") (pinfunction "B_3") (pintype "passive"))
      (node (ref "R27") (pin "2") (pinfunction "2_2") (pintype "passive"))
    )
    (net (code "58") (name "Net-(U1-A)") (class "Default")
      (node (ref "R1") (pin "2") (pinfunction "2_2") (pintype "passive"))
      (node (ref "U1") (pin "1") (pinfunction "A_1") (pintype "passive"))
    )
    (net (code "59") (name "Net-(U1-E)") (class "Default")
      (node (ref "R2") (pin "1") (pinfunction "1_1") (pintype "passive"))
      (node (ref "U1") (pin "3") (pinfunction "E_3") (pintype "passive"))
    )
    (net (code "60") (name "Net-(U2-A)") (class "Default")
      (node (ref "R6") (pin "2") (pinfunction "2_2") (pintype "passive"))
      (node (ref "U2") (pin "1") (pinfunction "A_1") (pintype "passive"))
    )
    (net (code "61") (name "Net-(U2-E)") (class "Default")
      (node (ref "R7") (pin "1") (pinfunction "1_1") (pintype "passive"))
      (node (ref "U2") (pin "3") (pinfunction "E_3") (pintype "passive"))
    )
    (net (code "62") (name "Net-(U3-A)") (class "Default")
      (node (ref "R11") (pin "2") (pinfunction "2_2") (pintype "passive"))
      (node (ref "U3") (pin "1") (pinfunction "A_1") (pintype "passive"))
    )
    (net (code "63") (name "Net-(U3-E)") (class "Default")
      (node (ref "R12") (pin "1") (pinfunction "1_1") (pintype "passive"))
      (node (ref "U3") (pin "3") (pinfunction "E_3") (pintype "passive"))
    )
    (net (code "64") (name "Net-(U4-A)") (class "Default")
      (node (ref "R16") (pin "2") (pinfunction "2_2") (pintype "passive"))
      (node (ref "U4") (pin "1") (pinfunction "A_1") (pintype "passive"))
    )
    (net (code "65") (name "Net-(U4-E)") (class "Default")
      (node (ref "R17") (pin "1") (pinfunction "1_1") (pintype "passive"))
      (node (ref "U4") (pin "3") (pinfunction "E_3") (pintype "passive"))
    )
    (net (code "66") (name "Net-(U6-A)") (class "Default")
      (node (ref "R21") (pin "2") (pinfunction "2_2") (pintype "passive"))
      (node (ref "U6") (pin "1") (pinfunction "A_1") (pintype "passive"))
    )
    (net (code "67") (name "Net-(U6-E)") (class "Default")
      (node (ref "R22") (pin "1") (pinfunction "1_1") (pintype "passive"))
      (node (ref "U6") (pin "3") (pinfunction "E_3") (pintype "passive"))
    )
    (net (code "68") (name "Net-(U7-A)") (class "Default")
      (node (ref "R26") (pin "2") (pinfunction "2_2") (pintype "passive"))
      (node (ref "U7") (pin "1") (pinfunction "A_1") (pintype "passive"))
    )
    (net (code "69") (name "Net-(U7-E)") (class "Default")
      (node (ref "R27") (pin "1") (pinfunction "1_1") (pintype "passive"))
      (node (ref "U7") (pin "3") (pinfunction "E_3") (pintype "passive"))
    )
    (net (code "70") (name "VCC5") (class "Default")
      (node (ref "B1") (pin "2") (pinfunction "VIN_2") (pintype "passive"))
      (node (ref "C4") (pin "1") (pinfunction "1_1") (pintype "passive"))
      (node (ref "C7") (pin "1") (pinfunction "1_1") (pintype "passive"))
      (node (ref "D1") (pin "2") (pinfunction "K_2") (pintype "passive"))
      (node (ref "D2") (pin "2") (pinfunction "K_2") (pintype "passive"))
      (node (ref "D3") (pin "2") (pinfunction "K_2") (pintype "passive"))
      (node (ref "D4") (pin "2") (pinfunction "K_2") (pintype "passive"))
      (node (ref "D5") (pin "2") (pinfunction "K_2") (pintype "passive"))
      (node (ref "D6") (pin "2") (pinfunction "K_2") (pintype "passive"))
      (node (ref "RL1") (pin "3") (pinfunction "3_3") (pintype "passive"))
      (node (ref "RL2") (pin "3") (pinfunction "3_3") (pintype "passive"))
      (node (ref "RL3") (pin "3") (pinfunction "3_3") (pintype "passive"))
      (node (ref "RL4") (pin "3") (pinfunction "3_3") (pintype "passive"))
      (node (ref "RL5") (pin "3") (pinfunction "3_3") (pintype "passive"))
      (node (ref "RL6") (pin "3") (pinfunction "3_3") (pintype "passive"))
      (node (ref "U1") (pin "4") (pinfunction "C_4") (pintype "passive"))
      (node (ref "U2") (pin "4") (pinfunction "C_4") (pintype "passive"))
      (node (ref "U3") (pin "4") (pinfunction "C_4") (pintype "passive"))
      (node (ref "U4") (pin "4") (pinfunction "C_4") (pintype "passive"))
      (node (ref "U6") (pin "4") (pinfunction "C_4") (pintype "passive"))
      (node (ref "U7") (pin "4") (pinfunction "C_4") (pintype "passive"))
      (node (ref "UN1") (pin "3") (pinfunction "OUT_3") (pintype "power_in"))
    )
    (net (code "71") (name "VCC5_ISO") (class "Default")
      (node (ref "Arduino1") (pin "VIN") (pinfunction "VIN_VIN") (pintype "passive"))
      (node (ref "B1") (pin "4") (pinfunction "+VO_4") (pintype "passive"))
      (node (ref "C11") (pin "3") (pinfunction "3_3") (pintype "passive"))
      (node (ref "C13") (pin "3") (pinfunction "3_3") (pintype "passive"))
      (node (ref "C2") (pin "1") (pinfunction "1_1") (pintype "passive"))
      (node (ref "LED1") (pin "1") (pinfunction "A_1") (pintype "passive"))
      (node (ref "LED10") (pin "1") (pinfunction "A_1") (pintype "passive"))
      (node (ref "LED3") (pin "1") (pinfunction "A_1") (pintype "passive"))
      (node (ref "LED5") (pin "1") (pinfunction "A_1") (pintype "passive"))
      (node (ref "LED8") (pin "1") (pinfunction "A_1") (pintype "passive"))
      (node (ref "R13") (pin "2") (pinfunction "2_2") (pintype "passive"))
      (node (ref "R18") (pin "2") (pinfunction "2_2") (pintype "passive"))
      (node (ref "R23") (pin "2") (pinfunction "2_2") (pintype "passive"))
      (node (ref "R3") (pin "2") (pinfunction "2_2") (pintype "passive"))
      (node (ref "R8") (pin "2") (pinfunction "2_2") (pintype "passive"))
      (node (ref "U5") (pin "2") (pinfunction "VCC_2") (pintype "passive"))
    )
    (net (code "72") (name "unconnected-(Arduino1-Pad3V3)") (class "Default")
      (node (ref "Arduino1") (pin "3V3") (pinfunction "3V3_3V3") (pintype "passive+no_connect"))
    )
    (net (code "73") (name "unconnected-(Arduino1-Pad5V)") (class "Default")
      (node (ref "Arduino1") (pin "5V") (pinfunction "5V_5V") (pintype "passive+no_connect"))
    )
    (net (code "74") (name "unconnected-(Arduino1-PadA0)") (class "Default")
      (node (ref "Arduino1") (pin "A0") (pinfunction "A0_A0") (pintype "passive+no_connect"))
    )
    (net (code "75") (name "unconnected-(Arduino1-PadA1)") (class "Default")
      (node (ref "Arduino1") (pin "A1") (pinfunction "A1_A1") (pintype "passive+no_connect"))
    )
    (net (code "76") (name "unconnected-(Arduino1-PadA3)") (class "Default")
      (node (ref "Arduino1") (pin "A3") (pinfunction "A3_A3") (pintype "passive+no_connect"))
    )
    (net (code "77") (name "unconnected-(Arduino1-PadA6)") (class "Default")
      (node (ref "Arduino1") (pin "A6") (pinfunction "A6_A6") (pintype "passive+no_connect"))
    )
    (net (code "78") (name "unconnected-(Arduino1-PadA7)") (class "Default")
      (node (ref "Arduino1") (pin "A7") (pinfunction "A7_A7") (pintype "passive+no_connect"))
    )
    (net (code "79") (name "unconnected-(Arduino1-PadD13)") (class "Default")
      (node (ref "Arduino1") (pin "D13") (pinfunction "D13_D13") (pintype "passive+no_connect"))
    )
    (net (code "80") (name "unconnected-(Arduino1-PadREF)") (class "Default")
      (node (ref "Arduino1") (pin "REF") (pinfunction "REF_REF") (pintype "passive+no_connect"))
    )
    (net (code "81") (name "unconnected-(Arduino1-PadRST)") (class "Default")
      (node (ref "Arduino1") (pin "RST") (pinfunction "RST_RST") (pintype "passive+no_connect"))
    )
    (net (code "82") (name "unconnected-(Arduino1-PadRST)_1") (class "Default")
      (node (ref "Arduino1") (pin "RST") (pinfunction "RST_RST") (pintype "passive+no_connect"))
    )
    (net (code "83") (name "unconnected-(Arduino1-PadRX0)") (class "Default")
      (node (ref "Arduino1") (pin "RX0") (pinfunction "RX0_RX0") (pintype "passive+no_connect"))
    )
    (net (code "84") (name "unconnected-(Arduino1-PadTX1)") (class "Default")
      (node (ref "Arduino1") (pin "TX1") (pinfunction "TX1_TX1") (pintype "passive+no_connect"))
    )
    (net (code "85") (name "unconnected-(JACK DC1-S-Pad3)") (class "Default")
      (node (ref "JACK DC1") (pin "3") (pinfunction "S_3") (pintype "power_in+no_connect"))
    )
    (net (code "86") (name "unconnected-(RL1-Pad2)") (class "Default")
      (node (ref "RL1") (pin "2") (pinfunction "2_2") (pintype "passive"))
    )
    (net (code "87") (name "unconnected-(RL2-Pad2)") (class "Default")
      (node (ref "RL2") (pin "2") (pinfunction "2_2") (pintype "passive"))
    )
    (net (code "88") (name "unconnected-(RL3-Pad2)") (class "Default")
      (node (ref "RL3") (pin "2") (pinfunction "2_2") (pintype "passive"))
    )
    (net (code "89") (name "unconnected-(RL4-Pad2)") (class "Default")
      (node (ref "RL4") (pin "2") (pinfunction "2_2") (pintype "passive"))
    )
    (net (code "90") (name "unconnected-(RL5-Pad2)") (class "Default")
      (node (ref "RL5") (pin "2") (pinfunction "2_2") (pintype "passive"))
    )
    (net (code "91") (name "unconnected-(RL6-Pad2)") (class "Default")
      (node (ref "RL6") (pin "2") (pinfunction "2_2") (pintype "passive"))
    )
    (net (code "92") (name "unconnected-(U5-BAT-Pad12)") (class "Default")
      (node (ref "U5") (pin "12") (pinfunction "BAT_12") (pintype "passive+no_connect"))
    )
    (net (code "93") (name "unconnected-(U5-DS-Pad5)") (class "Default")
      (node (ref "U5") (pin "5") (pinfunction "DS_5") (pintype "passive+no_connect"))
    )
    (net (code "94") (name "unconnected-(U5-DS-Pad7)") (class "Default")
      (node (ref "U5") (pin "7") (pinfunction "DS_7") (pintype "passive+no_connect"))
    )
    (net (code "95") (name "unconnected-(U5-GND-Pad11)") (class "Default")
      (node (ref "U5") (pin "11") (pinfunction "GND_11") (pintype "passive+no_connect"))
    )
    (net (code "96") (name "unconnected-(U5-SCL-Pad8)") (class "Default")
      (node (ref "U5") (pin "8") (pinfunction "SCL_8") (pintype "passive+no_connect"))
    )
    (net (code "97") (name "unconnected-(U5-SDA-Pad9)") (class "Default")
      (node (ref "U5") (pin "9") (pinfunction "SDA_9") (pintype "passive+no_connect"))
    )
    (net (code "98") (name "unconnected-(U5-SQ-Pad6)") (class "Default")
      (node (ref "U5") (pin "6") (pinfunction "SQ_6") (pintype "passive+no_connect"))
    )
    (net (code "99") (name "unconnected-(U5-VCC-Pad10)") (class "Default")
      (node (ref "U5") (pin "10") (pinfunction "VCC_10") (pintype "passive+no_connect"))
    )
  )
)
